# LED_Board_control.net
KiCad netlist of a schematic drawn in Altium Designer
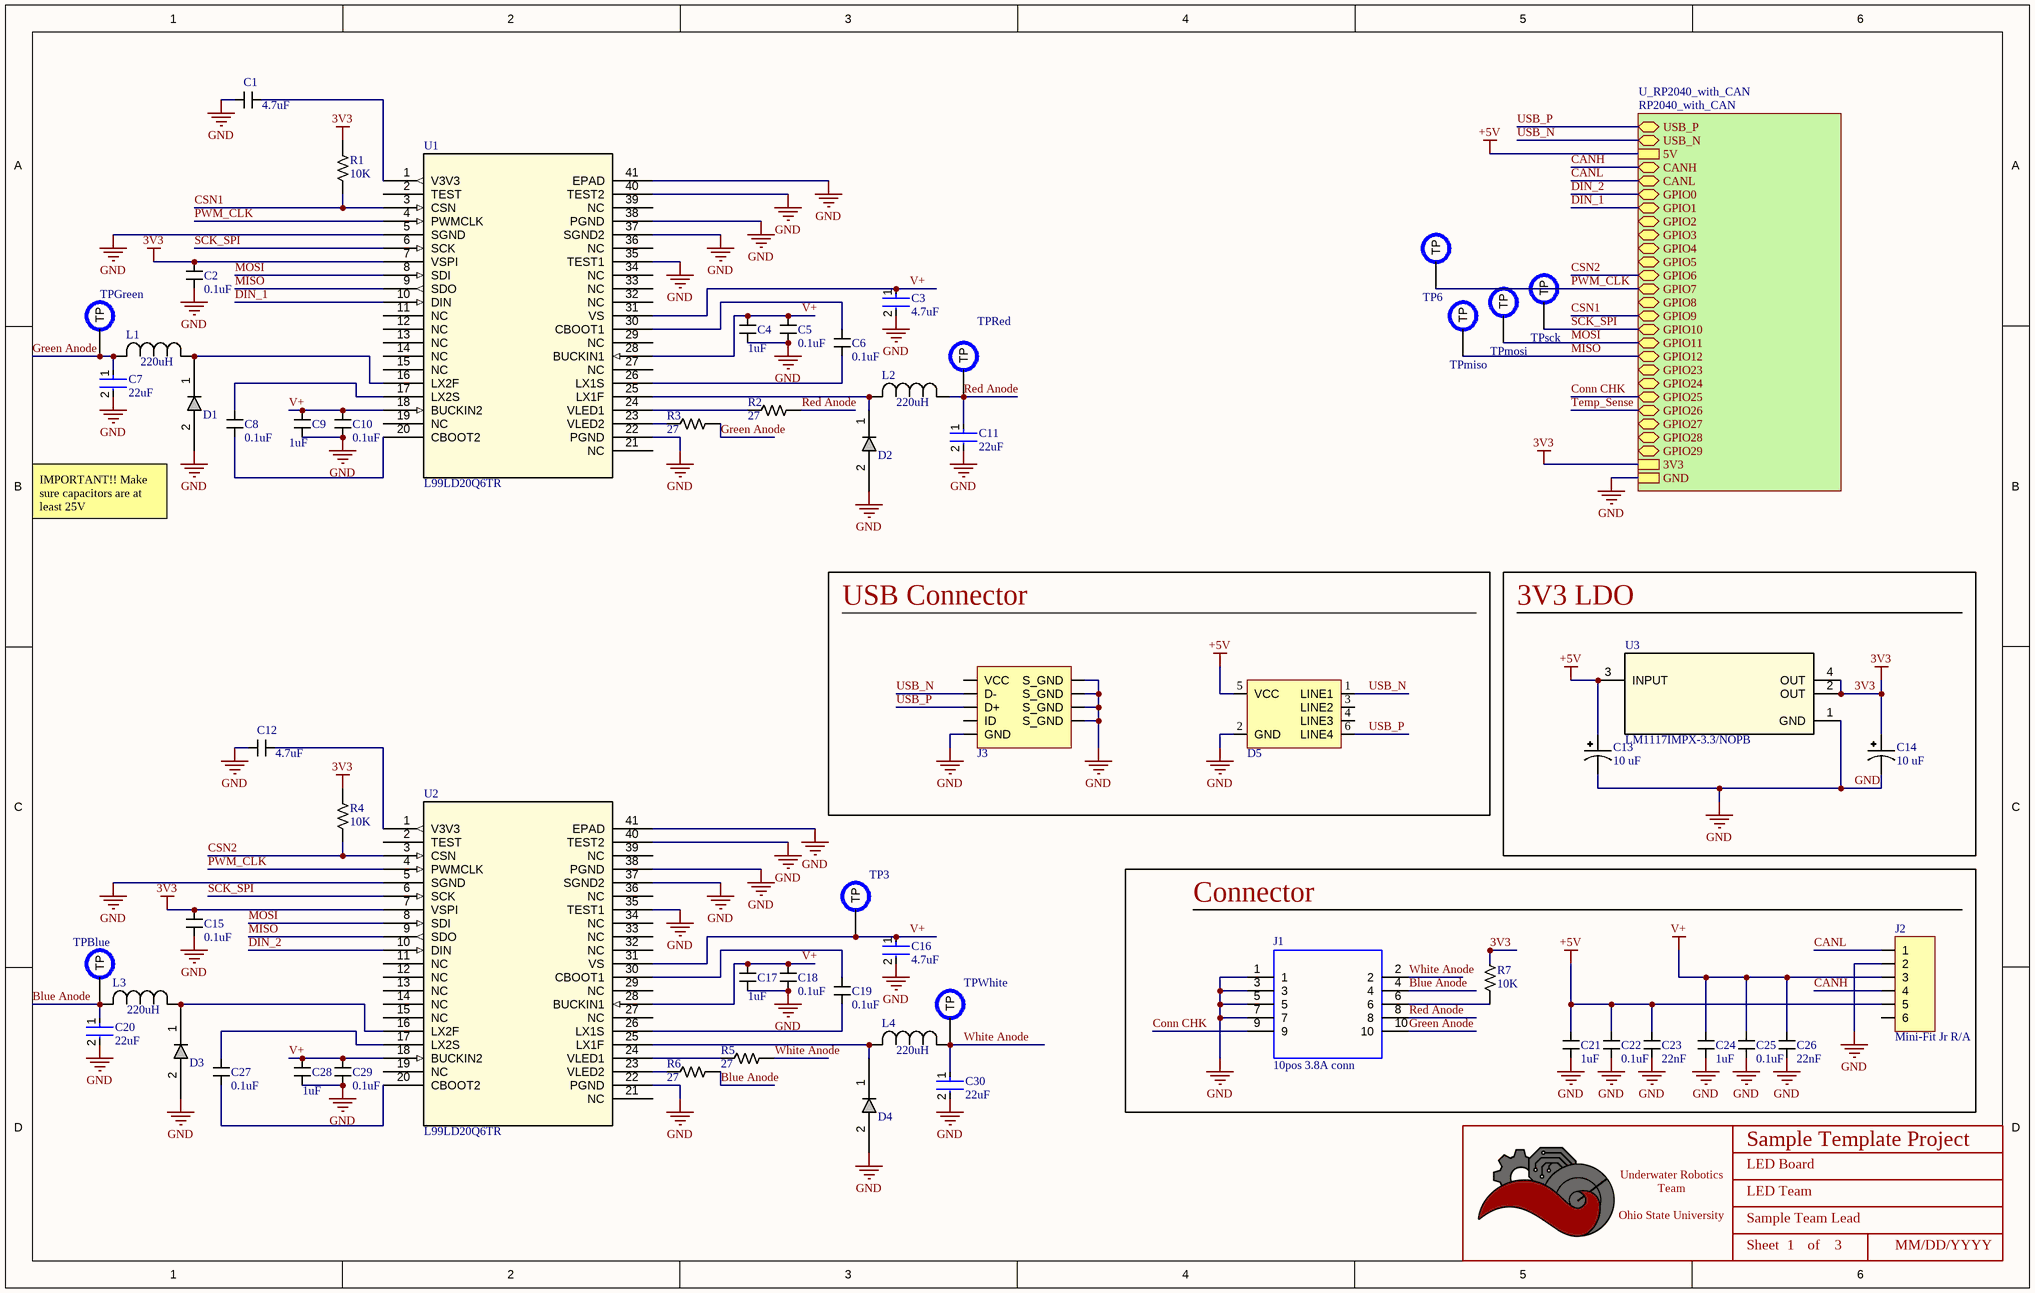
[diagram p0: LED_Board_control.SchDoc]

(export (version "E")
  (design (tool "Eeschema 10.0.6"))
  (components
    (comp (ref "*")
      (value "Title_Block")
      (footprint "LOGO")
      (description "UWRT Schematic Title Block Template\r\n\r\nCreated June 2021, Dylan Trainor")
      (libsource (lib "UWRT") (part "Title_Block"))
    )
    (comp (ref "C1")
      (value "4.7uF")
      (footprint "CAPACITOR_0603")
      (description "Cap 4.7uF 6.3V +/-10%\r\nCeramic 0603")
      (fields
        (field (name "TOLERANCE") "+/- 10%")
        (field (name "VOLTAGE") "6.3V")
        (field (name "MADE BY") "Robert Pafford")
      )
      (libsource (lib "Capacitors") (part "CAPACITOR_4.7uF_0603"))
    )
    (comp (ref "C2")
      (value "0.1uF")
      (footprint "CAPACITOR_0603")
      (description "Cap 100nF 6.3V +/-10%\r\nCeramic 0603")
      (fields
        (field (name "TOLERANCE") "+/- 10%")
        (field (name "VOLTAGE") "6.3V")
        (field (name "MADE BY") "Flip B")
      )
      (libsource (lib "Capacitors") (part "CAPACITOR_0.1uF_0603_1"))
    )
    (comp (ref "C3")
      (value "4.7uF")
      (footprint "CAPACITOR_0603")
      (description "Chip Multilayer Ceramic Capacitors for General Purpose, 0603, 4.7uF, X5R, 15%, 20%, 35V")
      (fields (field (name "TOLERANCE") "20%"))
      (libsource (lib "Capacitors") (part "CAP CERM 4.7UF 20% 35V"))
    )
    (comp (ref "C4")
      (value "1uF")
      (footprint "CAPACITOR_0603")
      (description "Cap 1uF 25V +/-10%\r\nCeramic 0603")
      (fields
        (field (name "TOLERANCE") "+/- 10%")
        (field (name "VOLTAGE") "16V")
        (field (name "MADE BY") "Flip B")
      )
      (libsource (lib "Capacitors") (part "CAPACITOR_1uF_0603_25V"))
    )
    (comp (ref "C5")
      (value "0.1uF")
      (footprint "CAPACITOR_0603")
      (description "Cap 100nF 25V +/-10%\r\nCeramic 0603")
      (fields
        (field (name "TOLERANCE") "+/- 10%")
        (field (name "VOLTAGE") "6.3V")
        (field (name "MADE BY") "Flip B")
      )
      (libsource (lib "Capacitors") (part "CAPACITOR_0.1uF_0603_25V"))
    )
    (comp (ref "C6")
      (value "0.1uF")
      (footprint "CAPACITOR_0603")
      (description "Cap 100nF 25V +/-10%\r\nCeramic 0603")
      (fields
        (field (name "TOLERANCE") "+/- 10%")
        (field (name "VOLTAGE") "6.3V")
        (field (name "MADE BY") "Flip B")
      )
      (libsource (lib "Capacitors") (part "CAPACITOR_0.1uF_0603_25V"))
    )
    (comp (ref "C7")
      (value "22uF")
      (footprint "FP-C2012-125-0_2-MFG")
      (description "Multilayer Ceramic Capacitors 22μF ±20% 35V X5R SMD 0805")
      (fields (field (name "TOLERANCE") "20%"))
      (libsource (lib "Altium Content Vault") (part "b4654b650e69147ec39a6b967a45e02"))
    )
    (comp (ref "C8")
      (value "0.1uF")
      (footprint "CAPACITOR_0603")
      (description "Cap 100nF 25V +/-10%\r\nCeramic 0603")
      (fields
        (field (name "TOLERANCE") "+/- 10%")
        (field (name "VOLTAGE") "6.3V")
        (field (name "MADE BY") "Flip B")
      )
      (libsource (lib "Capacitors") (part "CAPACITOR_0.1uF_0603_25V"))
    )
    (comp (ref "C9")
      (value "1uF")
      (footprint "CAPACITOR_0603")
      (description "Cap 1uF 25V +/-10%\r\nCeramic 0603")
      (fields
        (field (name "TOLERANCE") "+/- 10%")
        (field (name "VOLTAGE") "16V")
        (field (name "MADE BY") "Flip B")
      )
      (libsource (lib "Capacitors") (part "CAPACITOR_1uF_0603_25V"))
    )
    (comp (ref "C10")
      (value "0.1uF")
      (footprint "CAPACITOR_0603")
      (description "Cap 100nF 25V +/-10%\r\nCeramic 0603")
      (fields
        (field (name "TOLERANCE") "+/- 10%")
        (field (name "VOLTAGE") "6.3V")
        (field (name "MADE BY") "Flip B")
      )
      (libsource (lib "Capacitors") (part "CAPACITOR_0.1uF_0603_25V"))
    )
    (comp (ref "C11")
      (value "22uF")
      (footprint "FP-C2012-125-0_2-MFG")
      (description "Multilayer Ceramic Capacitors 22μF ±20% 35V X5R SMD 0805")
      (fields (field (name "TOLERANCE") "20%"))
      (libsource (lib "Altium Content Vault") (part "b4654b650e69147ec39a6b967a45e02"))
    )
    (comp (ref "C12")
      (value "4.7uF")
      (footprint "CAPACITOR_0603")
      (description "Cap 4.7uF 6.3V +/-10%\r\nCeramic 0603")
      (fields
        (field (name "TOLERANCE") "+/- 10%")
        (field (name "VOLTAGE") "6.3V")
        (field (name "MADE BY") "Robert Pafford")
      )
      (libsource (lib "Capacitors") (part "CAPACITOR_4.7uF_0603"))
    )
    (comp (ref "C13")
      (value "10uF Tantalum 16V")
      (footprint "CAPACITOR_1206 - POLAR")
      (description "Cap 10uF 16V +/-20%\r\nTantalum 1206")
      (fields
        (field (name "TOLERANCE") "+/- 10%")
        (field (name "VOLTAGE") "16V")
        (field (name "VALUE (UF)") "10 uF")
        (field (name "MADE BY") "Dylan T")
      )
      (libsource (lib "Capacitors") (part "CAPACITOR_10uF_1206_Tantalum_1"))
    )
    (comp (ref "C14")
      (value "10uF Tantalum 16V")
      (footprint "CAPACITOR_1206 - POLAR")
      (description "Cap 10uF 16V +/-20%\r\nTantalum 1206")
      (fields
        (field (name "TOLERANCE") "+/- 10%")
        (field (name "VOLTAGE") "16V")
        (field (name "VALUE (UF)") "10 uF")
        (field (name "MADE BY") "Dylan T")
      )
      (libsource (lib "Capacitors") (part "CAPACITOR_10uF_1206_Tantalum_1"))
    )
    (comp (ref "C15")
      (value "0.1uF")
      (footprint "CAPACITOR_0603")
      (description "Cap 100nF 6.3V +/-10%\r\nCeramic 0603")
      (fields
        (field (name "TOLERANCE") "+/- 10%")
        (field (name "VOLTAGE") "6.3V")
        (field (name "MADE BY") "Flip B")
      )
      (libsource (lib "Capacitors") (part "CAPACITOR_0.1uF_0603_1"))
    )
    (comp (ref "C16")
      (value "4.7uF")
      (footprint "CAPACITOR_0603")
      (description "Chip Multilayer Ceramic Capacitors for General Purpose, 0603, 4.7uF, X5R, 15%, 20%, 35V")
      (fields (field (name "TOLERANCE") "20%"))
      (libsource (lib "Capacitors") (part "CAP CERM 4.7UF 20% 35V"))
    )
    (comp (ref "C17")
      (value "1uF")
      (footprint "CAPACITOR_0603")
      (description "Cap 1uF 25V +/-10%\r\nCeramic 0603")
      (fields
        (field (name "TOLERANCE") "+/- 10%")
        (field (name "VOLTAGE") "16V")
        (field (name "MADE BY") "Flip B")
      )
      (libsource (lib "Capacitors") (part "CAPACITOR_1uF_0603_25V"))
    )
    (comp (ref "C18")
      (value "0.1uF")
      (footprint "CAPACITOR_0603")
      (description "Cap 100nF 25V +/-10%\r\nCeramic 0603")
      (fields
        (field (name "TOLERANCE") "+/- 10%")
        (field (name "VOLTAGE") "6.3V")
        (field (name "MADE BY") "Flip B")
      )
      (libsource (lib "Capacitors") (part "CAPACITOR_0.1uF_0603_25V"))
    )
    (comp (ref "C19")
      (value "0.1uF")
      (footprint "CAPACITOR_0603")
      (description "Cap 100nF 25V +/-10%\r\nCeramic 0603")
      (fields
        (field (name "TOLERANCE") "+/- 10%")
        (field (name "VOLTAGE") "6.3V")
        (field (name "MADE BY") "Flip B")
      )
      (libsource (lib "Capacitors") (part "CAPACITOR_0.1uF_0603_25V"))
    )
    (comp (ref "C20")
      (value "22uF")
      (footprint "FP-C2012-125-0_2-MFG")
      (description "Multilayer Ceramic Capacitors 22μF ±20% 35V X5R SMD 0805")
      (fields (field (name "TOLERANCE") "20%"))
      (libsource (lib "Altium Content Vault") (part "b4654b650e69147ec39a6b967a45e02"))
    )
    (comp (ref "C21")
      (value "1uF")
      (footprint "CAPACITOR_0603")
      (description "Cap 1uF 16V +/-10%\r\nCeramic 0603")
      (fields
        (field (name "TOLERANCE") "+/- 10%")
        (field (name "VOLTAGE") "16V")
        (field (name "MADE BY") "Flip B")
      )
      (libsource (lib "Capacitors") (part "CAPACITOR_1uF_0603"))
    )
    (comp (ref "C22")
      (value "0.1uF")
      (footprint "CAPACITOR_0805")
      (description "Cap 100nF 50V +/-10%\r\nCeramic 0805")
      (fields
        (field (name "TOLERANCE") "+/- 10%")
        (field (name "VOLTAGE") "50V")
        (field (name "MADE BY") "Robert Pafford")
      )
      (libsource (lib "Capacitors") (part "CAPACITOR_0.1uF_0805"))
    )
    (comp (ref "C23")
      (value "22nF")
      (footprint "CAPACITOR_0402")
      (description "Cap 22nF 25V +/-10%\r\nCeramic 0402")
      (fields
        (field (name "TOLERANCE") "+/- 10%")
        (field (name "VOLTAGE") "25V")
        (field (name "MADE BY") "Robert Pafford")
      )
      (libsource (lib "Capacitors") (part "CAPACITOR_0.022uF_0402"))
    )
    (comp (ref "C24")
      (value "1uF")
      (footprint "CAPACITOR_0603")
      (description "Cap 1uF 16V +/-10%\r\nCeramic 0603")
      (fields
        (field (name "TOLERANCE") "+/- 10%")
        (field (name "VOLTAGE") "16V")
        (field (name "MADE BY") "Flip B")
      )
      (libsource (lib "Capacitors") (part "CAPACITOR_1uF_0603"))
    )
    (comp (ref "C25")
      (value "0.1uF")
      (footprint "CAPACITOR_0805")
      (description "Cap 100nF 50V +/-10%\r\nCeramic 0805")
      (fields
        (field (name "TOLERANCE") "+/- 10%")
        (field (name "VOLTAGE") "50V")
        (field (name "MADE BY") "Robert Pafford")
      )
      (libsource (lib "Capacitors") (part "CAPACITOR_0.1uF_0805"))
    )
    (comp (ref "C26")
      (value "22nF")
      (footprint "CAPACITOR_0402")
      (description "Cap 22nF 25V +/-10%\r\nCeramic 0402")
      (fields
        (field (name "TOLERANCE") "+/- 10%")
        (field (name "VOLTAGE") "25V")
        (field (name "MADE BY") "Robert Pafford")
      )
      (libsource (lib "Capacitors") (part "CAPACITOR_0.022uF_0402"))
    )
    (comp (ref "C27")
      (value "0.1uF")
      (footprint "CAPACITOR_0603")
      (description "Cap 100nF 25V +/-10%\r\nCeramic 0603")
      (fields
        (field (name "TOLERANCE") "+/- 10%")
        (field (name "VOLTAGE") "6.3V")
        (field (name "MADE BY") "Flip B")
      )
      (libsource (lib "Capacitors") (part "CAPACITOR_0.1uF_0603_25V"))
    )
    (comp (ref "C28")
      (value "1uF")
      (footprint "CAPACITOR_0603")
      (description "Cap 1uF 25V +/-10%\r\nCeramic 0603")
      (fields
        (field (name "TOLERANCE") "+/- 10%")
        (field (name "VOLTAGE") "16V")
        (field (name "MADE BY") "Flip B")
      )
      (libsource (lib "Capacitors") (part "CAPACITOR_1uF_0603_25V"))
    )
    (comp (ref "C29")
      (value "0.1uF")
      (footprint "CAPACITOR_0603")
      (description "Cap 100nF 25V +/-10%\r\nCeramic 0603")
      (fields
        (field (name "TOLERANCE") "+/- 10%")
        (field (name "VOLTAGE") "6.3V")
        (field (name "MADE BY") "Flip B")
      )
      (libsource (lib "Capacitors") (part "CAPACITOR_0.1uF_0603_25V"))
    )
    (comp (ref "C30")
      (value "22uF")
      (footprint "FP-C2012-125-0_2-MFG")
      (description "Multilayer Ceramic Capacitors 22μF ±20% 35V X5R SMD 0805")
      (fields (field (name "TOLERANCE") "20%"))
      (libsource (lib "Altium Content Vault") (part "b4654b650e69147ec39a6b967a45e02"))
    )
    (comp (ref "D1")
      (value "CCS15S40,L3F")
      (footprint "SOD-963   CST2C_TOS")
      (description "DIODE SCHOTTKY 40V 1.5A CST2C")
      (fields (field (name "COPYRIGHT") "Copyright (C) 2023 Ultra Librarian. All rights reserved."))
      (libsource (lib "Diodes") (part "SCHOTTKY_40V_1.5A"))
    )
    (comp (ref "D2")
      (value "CCS15S40,L3F")
      (footprint "SOD-963   CST2C_TOS")
      (description "DIODE SCHOTTKY 40V 1.5A CST2C")
      (fields (field (name "COPYRIGHT") "Copyright (C) 2023 Ultra Librarian. All rights reserved."))
      (libsource (lib "Diodes") (part "SCHOTTKY_40V_1.5A"))
    )
    (comp (ref "D3")
      (value "CCS15S40,L3F")
      (footprint "SOD-963   CST2C_TOS")
      (description "DIODE SCHOTTKY 40V 1.5A CST2C")
      (fields (field (name "COPYRIGHT") "Copyright (C) 2023 Ultra Librarian. All rights reserved."))
      (libsource (lib "Diodes") (part "SCHOTTKY_40V_1.5A"))
    )
    (comp (ref "D4")
      (value "CCS15S40,L3F")
      (footprint "SOD-963   CST2C_TOS")
      (description "DIODE SCHOTTKY 40V 1.5A CST2C")
      (fields (field (name "COPYRIGHT") "Copyright (C) 2023 Ultra Librarian. All rights reserved."))
      (libsource (lib "Diodes") (part "SCHOTTKY_40V_1.5A"))
    )
    (comp (ref "D5")
      (value "TVS DIODE 5VWM 25VC SOT23-6")
      (footprint "SOT 23-6L")
      (description "25V Clamp 6A (8/20µs) Ipp Tvs Diode Surface Mount SOT-23-6")
      (fields (field (name "MADE BY") "Robert Pafford"))
      (libsource (lib "Diodes") (part "RCLAMP0504S.TCT"))
    )
    (comp (ref "J1")
      (value "10pos 3.8A conn")
      (footprint "Connectors:SAMTEC-LS2-105-01-X-D-RA1")
      (description "10 Position Connector Self Mating, Non-Gendered, Hermaphroditic Through Hole, Right Angle Gold")
      (fields (field (name "MP") "SAMTEC-LS2-105-01-X-D-RA1"))
      (libsource (lib "Connectors") (part "SAMTEC-LS2-105-01-X-D-RA1"))
    )
    (comp (ref "J2")
      (value "Mini-Fit Jr R/A")
      (footprint "CONN_MOLEX_MINIFIT JR_6 POS_R/A")
      (description "Molex Minifit Jr. 5569 \r\n6 Pos R/A Natural")
      (fields (field (name "MANUFACTURER") "Molex") (field (name "CREATED BY") "Flip B"))
      (libsource (lib "Connectors") (part "CONN_MOLEX_MINIFIT JR_6POS_R/A"))
    )
    (comp (ref "J3")
      (value "USB_MICRO R/A")
      (footprint "CONN_MINIUSB")
      (description "Amphenol Micro USB-B\r\nUSB2.0 5 Pin Right Angle SMD")
      (fields (field (name "MANUFACTURER") "Amphenol") (field (name "CREATED BY") "Flip B"))
      (libsource (lib "Connectors") (part "CONN_MICROUSB"))
    )
    (comp (ref "L1")
      (value "SRR1280-221K")
      (footprint "IND_BOURNS_SRR1280")
      (description "220 µH Shielded Drum Core, Wirewound Inductor 1.6 A 400mOhm Max Nonstandard")
      (fields (field (name "COPYRIGHT") "Copyright (C) 2023 Ultra Librarian. All rights reserved."))
      (libsource (lib "Inductors") (part "INDUCTOR_SRR1280-221K"))
    )
    (comp (ref "L2")
      (value "SRR1280-221K")
      (footprint "IND_BOURNS_SRR1280")
      (description "220 µH Shielded Drum Core, Wirewound Inductor 1.6 A 400mOhm Max Nonstandard")
      (fields (field (name "COPYRIGHT") "Copyright (C) 2023 Ultra Librarian. All rights reserved."))
      (libsource (lib "Inductors") (part "INDUCTOR_SRR1280-221K"))
    )
    (comp (ref "L3")
      (value "SRR1280-221K")
      (footprint "IND_BOURNS_SRR1280")
      (description "220 µH Shielded Drum Core, Wirewound Inductor 1.6 A 400mOhm Max Nonstandard")
      (fields (field (name "COPYRIGHT") "Copyright (C) 2023 Ultra Librarian. All rights reserved."))
      (libsource (lib "Inductors") (part "INDUCTOR_SRR1280-221K"))
    )
    (comp (ref "L4")
      (value "SRR1280-221K")
      (footprint "IND_BOURNS_SRR1280")
      (description "220 µH Shielded Drum Core, Wirewound Inductor 1.6 A 400mOhm Max Nonstandard")
      (fields (field (name "COPYRIGHT") "Copyright (C) 2023 Ultra Librarian. All rights reserved."))
      (libsource (lib "Inductors") (part "INDUCTOR_SRR1280-221K"))
    )
    (comp (ref "R1")
      (value "10k Ohm 1% 1/16W")
      (footprint "RESISTOR_0402")
      (description "RES 10k OHM 1% 1/16W 0402")
      (fields
        (field (name "TOLERANCE") "+/- 1%")
        (field (name "VALUE  (OHMS)") "10K")
        (field (name "MADE BY") "Robert Pafford")
      )
      (libsource (lib "Resistors") (part "RESISTOR_10K_0402"))
    )
    (comp (ref "R2")
      (value "27 Ohm 5% 1/8W")
      (footprint "RESISTOR_0603")
      (description "RES 27 OHM 5% 1/8W 0603")
      (fields
        (field (name "TOLERANCE") "+/- 5%")
        (field (name "VALUE  (OHMS)") "27")
        (field (name "MADE BY") "Robert Pafford")
      )
      (libsource (lib "Resistors") (part "RESISTOR_27_0603"))
    )
    (comp (ref "R3")
      (value "27 Ohm 5% 1/8W")
      (footprint "RESISTOR_0603")
      (description "RES 27 OHM 5% 1/8W 0603")
      (fields
        (field (name "TOLERANCE") "+/- 5%")
        (field (name "VALUE  (OHMS)") "27")
        (field (name "MADE BY") "Robert Pafford")
      )
      (libsource (lib "Resistors") (part "RESISTOR_27_0603"))
    )
    (comp (ref "R4")
      (value "10k Ohm 1% 1/16W")
      (footprint "RESISTOR_0402")
      (description "RES 10k OHM 1% 1/16W 0402")
      (fields
        (field (name "TOLERANCE") "+/- 1%")
        (field (name "VALUE  (OHMS)") "10K")
        (field (name "MADE BY") "Robert Pafford")
      )
      (libsource (lib "Resistors") (part "RESISTOR_10K_0402"))
    )
    (comp (ref "R5")
      (value "27 Ohm 5% 1/8W")
      (footprint "RESISTOR_0603")
      (description "RES 27 OHM 5% 1/8W 0603")
      (fields
        (field (name "TOLERANCE") "+/- 5%")
        (field (name "VALUE  (OHMS)") "27")
        (field (name "MADE BY") "Robert Pafford")
      )
      (libsource (lib "Resistors") (part "RESISTOR_27_0603"))
    )
    (comp (ref "R6")
      (value "27 Ohm 5% 1/8W")
      (footprint "RESISTOR_0603")
      (description "RES 27 OHM 5% 1/8W 0603")
      (fields
        (field (name "TOLERANCE") "+/- 5%")
        (field (name "VALUE  (OHMS)") "27")
        (field (name "MADE BY") "Robert Pafford")
      )
      (libsource (lib "Resistors") (part "RESISTOR_27_0603"))
    )
    (comp (ref "R7")
      (value "10k Ohm 0.5% 1/10W")
      (footprint "RESISTOR_0603")
      (description "RES 10k OHM 0.5% 1/10W 0603")
      (fields
        (field (name "TOLERANCE") "+/- 0.5%")
        (field (name "VALUE  (OHMS)") "10K")
        (field (name "MADE BY") "Robert Pafford")
      )
      (libsource (lib "Resistors") (part "RESISTOR_10K_0.5%_0603"))
    )
    (comp (ref "TP3")
      (value "PCB Test Point")
      (footprint "TESTPOINT_1.2MM")
      (fields (field (name "MADE BY") "Robert Pafford"))
      (libsource (lib "Connectors") (part "TESTPOINT"))
    )
    (comp (ref "TP6")
      (value "PCB Test Point")
      (footprint "TESTPOINT_1.2MM")
      (fields (field (name "MADE BY") "Robert Pafford"))
      (libsource (lib "Connectors") (part "TESTPOINT"))
    )
    (comp (ref "TPBlue")
      (value "PCB Test Point")
      (footprint "TESTPOINT_1.2MM")
      (fields (field (name "MADE BY") "Robert Pafford"))
      (libsource (lib "Connectors") (part "TESTPOINT"))
    )
    (comp (ref "TPGreen")
      (value "PCB Test Point")
      (footprint "TESTPOINT_1.2MM")
      (fields (field (name "MADE BY") "Robert Pafford"))
      (libsource (lib "Connectors") (part "TESTPOINT"))
    )
    (comp (ref "TPmiso")
      (value "PCB Test Point")
      (footprint "TESTPOINT_1.2MM")
      (fields (field (name "MADE BY") "Robert Pafford"))
      (libsource (lib "Connectors") (part "TESTPOINT"))
    )
    (comp (ref "TPmosi")
      (value "PCB Test Point")
      (footprint "TESTPOINT_1.2MM")
      (fields (field (name "MADE BY") "Robert Pafford"))
      (libsource (lib "Connectors") (part "TESTPOINT"))
    )
    (comp (ref "TPRed")
      (value "PCB Test Point")
      (footprint "TESTPOINT_1.2MM")
      (fields (field (name "MADE BY") "Robert Pafford"))
      (libsource (lib "Connectors") (part "TESTPOINT"))
    )
    (comp (ref "TPsck")
      (value "PCB Test Point")
      (footprint "TESTPOINT_1.2MM")
      (fields (field (name "MADE BY") "Robert Pafford"))
      (libsource (lib "Connectors") (part "TESTPOINT"))
    )
    (comp (ref "TPWhite")
      (value "PCB Test Point")
      (footprint "TESTPOINT_1.2MM")
      (fields (field (name "MADE BY") "Robert Pafford"))
      (libsource (lib "Connectors") (part "TESTPOINT"))
    )
    (comp (ref "U1")
      (value "L99LD20Q6TR")
      (footprint "L99LD20Q6TR")
      (description "IC LED DRVR RGLTR PWM 1.5A 40QFN")
      (fields (field (name "COPYRIGHT") "Copyright (C) 2023 Ultra Librarian. All rights reserved."))
      (libsource (lib "Integrated Circuits") (part "L99LD20Q6TR"))
    )
    (comp (ref "U2")
      (value "L99LD20Q6TR")
      (footprint "L99LD20Q6TR")
      (description "IC LED DRVR RGLTR PWM 1.5A 40QFN")
      (fields (field (name "COPYRIGHT") "Copyright (C) 2023 Ultra Librarian. All rights reserved."))
      (libsource (lib "Integrated Circuits") (part "L99LD20Q6TR"))
    )
    (comp (ref "U3")
      (value "LM1117IMPX-3.3/NOPB")
      (footprint "SOT-223-4")
      (description "IC REG LIN 3.3V 800MA SOT223-4")
      (fields
        (field (name "PARTNUMBER") "LM1117IMP-3.3/NOPB")
        (field (name "MANUFACTURER") "Texas Instruments")
        (field (name "CREATED BY") "Dylan T")
      )
      (libsource (lib "Converter") (part "LM1117IMPX-3.3/NOPB"))
    )
  )
  (nets
    (net (code "1") (name "+5V") (class "Default")
      (node (ref "C13") (pin "1") (pintype "passive"))
      (node (ref "C21") (pin "1") (pinfunction "1_1") (pintype "passive"))
      (node (ref "C22") (pin "1") (pinfunction "1_1") (pintype "passive"))
      (node (ref "C23") (pin "1") (pinfunction "1_1") (pintype "passive"))
      (node (ref "D5") (pin "5") (pinfunction "VCC_5") (pintype "power_in"))
      (node (ref "J2") (pin "5") (pinfunction "5_5") (pintype "passive"))
      (node (ref "U3") (pin "3") (pinfunction "INPUT_3") (pintype "power_in"))
    )
    (net (code "2") (name "/Blue Anode") (class "Default")
      (node (ref "C20") (pin "1") (pinfunction "1_1") (pintype "passive"))
      (node (ref "J1") (pin "4") (pinfunction "4_4") (pintype "passive"))
      (node (ref "L3") (pin "2") (pinfunction "2_2") (pintype "passive"))
      (node (ref "R6") (pin "1") (pinfunction "1_1") (pintype "passive"))
      (node (ref "TPBlue") (pin "TP") (pinfunction "TP_TP") (pintype "passive"))
    )
    (net (code "3") (name "/CANH") (class "Default")
      (node (ref "J2") (pin "4") (pinfunction "4_4") (pintype "passive"))
    )
    (net (code "4") (name "/CANL") (class "Default")
      (node (ref "J2") (pin "1") (pinfunction "1_1") (pintype "passive"))
    )
    (net (code "5") (name "/CSN1") (class "Default")
      (node (ref "R1") (pin "2") (pinfunction "2_2") (pintype "passive"))
      (node (ref "U1") (pin "3") (pinfunction "CSN_3") (pintype "input"))
    )
    (net (code "6") (name "/CSN2") (class "Default")
      (node (ref "R4") (pin "2") (pinfunction "2_2") (pintype "passive"))
      (node (ref "U2") (pin "3") (pinfunction "CSN_3") (pintype "input"))
    )
    (net (code "7") (name "/Conn CHK") (class "Default")
      (node (ref "J1") (pin "9") (pinfunction "9_9") (pintype "passive"))
    )
    (net (code "8") (name "/DIN_1") (class "Default")
      (node (ref "U1") (pin "10") (pinfunction "DIN_10") (pintype "input"))
    )
    (net (code "9") (name "/DIN_2") (class "Default")
      (node (ref "U2") (pin "10") (pinfunction "DIN_10") (pintype "input"))
    )
    (net (code "20") (name "/Green Anode") (class "Default")
      (node (ref "C7") (pin "1") (pinfunction "1_1") (pintype "passive"))
      (node (ref "J1") (pin "10") (pinfunction "10_10") (pintype "passive"))
      (node (ref "L1") (pin "2") (pinfunction "2_2") (pintype "passive"))
      (node (ref "R3") (pin "1") (pinfunction "1_1") (pintype "passive"))
      (node (ref "TPGreen") (pin "TP") (pinfunction "TP_TP") (pintype "passive"))
    )
    (net (code "21") (name "/MISO") (class "Default")
      (node (ref "TPmiso") (pin "TP") (pinfunction "TP_TP") (pintype "passive"))
      (node (ref "U1") (pin "9") (pinfunction "SDO_9") (pintype "output"))
      (node (ref "U2") (pin "9") (pinfunction "SDO_9") (pintype "output"))
    )
    (net (code "22") (name "/MOSI") (class "Default")
      (node (ref "TPmosi") (pin "TP") (pinfunction "TP_TP") (pintype "passive"))
      (node (ref "U1") (pin "8") (pinfunction "SDI_8") (pintype "input"))
      (node (ref "U2") (pin "8") (pinfunction "SDI_8") (pintype "input"))
    )
    (net (code "23") (name "/PWM_CLK") (class "Default")
      (node (ref "TP6") (pin "TP") (pinfunction "TP_TP") (pintype "passive"))
      (node (ref "U1") (pin "4") (pinfunction "PWMCLK_4") (pintype "input"))
      (node (ref "U2") (pin "4") (pinfunction "PWMCLK_4") (pintype "input"))
    )
    (net (code "24") (name "/Red Anode") (class "Default")
      (node (ref "C11") (pin "1") (pinfunction "1_1") (pintype "passive"))
      (node (ref "J1") (pin "8") (pinfunction "8_8") (pintype "passive"))
      (node (ref "L2") (pin "1") (pinfunction "1_1") (pintype "passive"))
      (node (ref "R2") (pin "1") (pinfunction "1_1") (pintype "passive"))
      (node (ref "TPRed") (pin "TP") (pinfunction "TP_TP") (pintype "passive"))
    )
    (net (code "25") (name "/SCK_SPI") (class "Default")
      (node (ref "TPsck") (pin "TP") (pinfunction "TP_TP") (pintype "passive"))
      (node (ref "U1") (pin "6") (pinfunction "SCK_6") (pintype "input"))
      (node (ref "U2") (pin "6") (pinfunction "SCK_6") (pintype "input"))
    )
    (net (code "27") (name "/USB_N") (class "Default")
      (node (ref "D5") (pin "1") (pinfunction "LINE1_1") (pintype "passive"))
      (node (ref "J3") (pin "2") (pinfunction "D-_2") (pintype "passive"))
    )
    (net (code "28") (name "/USB_P") (class "Default")
      (node (ref "D5") (pin "6") (pinfunction "LINE4_6") (pintype "passive"))
      (node (ref "J3") (pin "3") (pinfunction "D+_3") (pintype "passive"))
    )
    (net (code "29") (name "/White Anode") (class "Default")
      (node (ref "C30") (pin "1") (pinfunction "1_1") (pintype "passive"))
      (node (ref "J1") (pin "2") (pinfunction "2_2") (pintype "passive"))
      (node (ref "L4") (pin "1") (pinfunction "1_1") (pintype "passive"))
      (node (ref "R5") (pin "1") (pinfunction "1_1") (pintype "passive"))
      (node (ref "TPWhite") (pin "TP") (pinfunction "TP_TP") (pintype "passive"))
    )
    (net (code "30") (name "3V3") (class "Default")
      (node (ref "C14") (pin "1") (pintype "passive"))
      (node (ref "C15") (pin "1") (pinfunction "1_1") (pintype "passive"))
      (node (ref "C2") (pin "1") (pinfunction "1_1") (pintype "passive"))
      (node (ref "R1") (pin "1") (pinfunction "1_1") (pintype "passive"))
      (node (ref "R4") (pin "1") (pinfunction "1_1") (pintype "passive"))
      (node (ref "R7") (pin "1") (pinfunction "1_1") (pintype "passive"))
      (node (ref "U1") (pin "7") (pinfunction "VSPI_7") (pintype "passive"))
      (node (ref "U2") (pin "7") (pinfunction "VSPI_7") (pintype "passive"))
      (node (ref "U3") (pin "2") (pinfunction "OUT_2") (pintype "power_in"))
      (node (ref "U3") (pin "4") (pinfunction "OUT_4") (pintype "power_in"))
    )
    (net (code "31") (name "GND") (class "Default")
      (node (ref "C1") (pin "2") (pinfunction "2_2") (pintype "passive"))
      (node (ref "C10") (pin "2") (pinfunction "2_2") (pintype "passive"))
      (node (ref "C11") (pin "2") (pinfunction "2_2") (pintype "passive"))
      (node (ref "C12") (pin "2") (pinfunction "2_2") (pintype "passive"))
      (node (ref "C13") (pin "2") (pintype "passive"))
      (node (ref "C14") (pin "2") (pintype "passive"))
      (node (ref "C15") (pin "2") (pinfunction "2_2") (pintype "passive"))
      (node (ref "C16") (pin "2") (pinfunction "2_2") (pintype "passive"))
      (node (ref "C17") (pin "1") (pinfunction "1_1") (pintype "passive"))
      (node (ref "C18") (pin "2") (pinfunction "2_2") (pintype "passive"))
      (node (ref "C2") (pin "2") (pinfunction "2_2") (pintype "passive"))
      (node (ref "C20") (pin "2") (pinfunction "2_2") (pintype "passive"))
      (node (ref "C21") (pin "2") (pinfunction "2_2") (pintype "passive"))
      (node (ref "C22") (pin "2") (pinfunction "2_2") (pintype "passive"))
      (node (ref "C23") (pin "2") (pinfunction "2_2") (pintype "passive"))
      (node (ref "C24") (pin "2") (pinfunction "2_2") (pintype "passive"))
      (node (ref "C25") (pin "2") (pinfunction "2_2") (pintype "passive"))
      (node (ref "C26") (pin "2") (pinfunction "2_2") (pintype "passive"))
      (node (ref "C28") (pin "1") (pinfunction "1_1") (pintype "passive"))
      (node (ref "C29") (pin "2") (pinfunction "2_2") (pintype "passive"))
      (node (ref "C3") (pin "2") (pinfunction "2_2") (pintype "passive"))
      (node (ref "C30") (pin "2") (pinfunction "2_2") (pintype "passive"))
      (node (ref "C4") (pin "1") (pinfunction "1_1") (pintype "passive"))
      (node (ref "C5") (pin "2") (pinfunction "2_2") (pintype "passive"))
      (node (ref "C7") (pin "2") (pinfunction "2_2") (pintype "passive"))
      (node (ref "C9") (pin "1") (pinfunction "1_1") (pintype "passive"))
      (node (ref "D1") (pin "2") (pinfunction "2_2") (pintype "passive"))
      (node (ref "D2") (pin "2") (pinfunction "2_2") (pintype "passive"))
      (node (ref "D3") (pin "2") (pinfunction "2_2") (pintype "passive"))
      (node (ref "D4") (pin "2") (pinfunction "2_2") (pintype "passive"))
      (node (ref "D5") (pin "2") (pinfunction "GND_2") (pintype "power_in"))
      (node (ref "J1") (pin "1") (pinfunction "1_1") (pintype "passive"))
      (node (ref "J1") (pin "3") (pinfunction "3_3") (pintype "passive"))
      (node (ref "J1") (pin "5") (pinfunction "5_5") (pintype "passive"))
      (node (ref "J1") (pin "7") (pinfunction "7_7") (pintype "passive"))
      (node (ref "J2") (pin "2") (pinfunction "2_2") (pintype "passive"))
      (node (ref "J3") (pin "5") (pinfunction "GND_5") (pintype "passive"))
      (node (ref "J3") (pin "6") (pinfunction "S_GND_6") (pintype "passive"))
      (node (ref "J3") (pin "7") (pinfunction "S_GND_7") (pintype "passive"))
      (node (ref "J3") (pin "8") (pinfunction "S_GND_8") (pintype "passive"))
      (node (ref "J3") (pin "9") (pinfunction "S_GND_9") (pintype "passive"))
      (node (ref "U1") (pin "22") (pinfunction "PGND_22") (pintype "power_in"))
      (node (ref "U1") (pin "35") (pinfunction "TEST1_35") (pintype "passive"))
      (node (ref "U1") (pin "37") (pinfunction "SGND2_37") (pintype "power_in"))
      (node (ref "U1") (pin "38") (pinfunction "PGND_38") (pintype "power_in"))
      (node (ref "U1") (pin "40") (pinfunction "TEST2_40") (pintype "passive"))
      (node (ref "U1") (pin "41") (pinfunction "EPAD_41") (pintype "power_in"))
      (node (ref "U1") (pin "5") (pinfunction "SGND_5") (pintype "power_in"))
      (node (ref "U2") (pin "22") (pinfunction "PGND_22") (pintype "power_in"))
      (node (ref "U2") (pin "35") (pinfunction "TEST1_35") (pintype "passive"))
      (node (ref "U2") (pin "37") (pinfunction "SGND2_37") (pintype "power_in"))
      (node (ref "U2") (pin "38") (pinfunction "PGND_38") (pintype "power_in"))
      (node (ref "U2") (pin "40") (pinfunction "TEST2_40") (pintype "passive"))
      (node (ref "U2") (pin "41") (pinfunction "EPAD_41") (pintype "power_in"))
      (node (ref "U2") (pin "5") (pinfunction "SGND_5") (pintype "power_in"))
      (node (ref "U3") (pin "1") (pinfunction "GND_1") (pintype "power_in"))
    )
    (net (code "32") (name "Net-(J1-Pad6)") (class "Default")
      (node (ref "J1") (pin "6") (pinfunction "6_6") (pintype "passive"))
      (node (ref "R7") (pin "2") (pinfunction "2_2") (pintype "passive"))
    )
    (net (code "33") (name "Net-(U1-CBOOT1)") (class "Default")
      (node (ref "C6") (pin "1") (pinfunction "1_1") (pintype "passive"))
      (node (ref "U1") (pin "30") (pinfunction "CBOOT1_30") (pintype "passive"))
    )
    (net (code "34") (name "Net-(U1-CBOOT2)") (class "Default")
      (node (ref "C8") (pin "2") (pinfunction "2_2") (pintype "passive"))
      (node (ref "U1") (pin "20") (pinfunction "CBOOT2_20") (pintype "passive"))
    )
    (net (code "35") (name "Net-(U1-LX1F)") (class "Default")
      (node (ref "D2") (pin "1") (pinfunction "1_1") (pintype "passive"))
      (node (ref "L2") (pin "2") (pinfunction "2_2") (pintype "passive"))
      (node (ref "U1") (pin "25") (pinfunction "LX1F_25") (pintype "passive"))
    )
    (net (code "36") (name "Net-(U1-LX1S)") (class "Default")
      (node (ref "C6") (pin "2") (pinfunction "2_2") (pintype "passive"))
      (node (ref "U1") (pin "26") (pinfunction "LX1S_26") (pintype "passive"))
    )
    (net (code "37") (name "Net-(U1-LX2F)") (class "Default")
      (node (ref "D1") (pin "1") (pinfunction "1_1") (pintype "passive"))
      (node (ref "L1") (pin "1") (pinfunction "1_1") (pintype "passive"))
      (node (ref "U1") (pin "16") (pinfunction "LX2F_16") (pintype "passive"))
    )
    (net (code "38") (name "Net-(U1-LX2S)") (class "Default")
      (node (ref "C8") (pin "1") (pinfunction "1_1") (pintype "passive"))
      (node (ref "U1") (pin "17") (pinfunction "LX2S_17") (pintype "passive"))
    )
    (net (code "39") (name "Net-(U1-V3V3)") (class "Default")
      (node (ref "C1") (pin "1") (pinfunction "1_1") (pintype "passive"))
      (node (ref "U1") (pin "1") (pinfunction "V3V3_1") (pintype "output"))
    )
    (net (code "40") (name "Net-(U1-VLED1)") (class "Default")
      (node (ref "R2") (pin "2") (pinfunction "2_2") (pintype "passive"))
      (node (ref "U1") (pin "24") (pinfunction "VLED1_24") (pintype "passive"))
    )
    (net (code "41") (name "Net-(U1-VLED2)") (class "Default")
      (node (ref "R3") (pin "2") (pinfunction "2_2") (pintype "passive"))
      (node (ref "U1") (pin "23") (pinfunction "VLED2_23") (pintype "passive"))
    )
    (net (code "42") (name "Net-(U2-CBOOT1)") (class "Default")
      (node (ref "C19") (pin "1") (pinfunction "1_1") (pintype "passive"))
      (node (ref "U2") (pin "30") (pinfunction "CBOOT1_30") (pintype "passive"))
    )
    (net (code "43") (name "Net-(U2-CBOOT2)") (class "Default")
      (node (ref "C27") (pin "2") (pinfunction "2_2") (pintype "passive"))
      (node (ref "U2") (pin "20") (pinfunction "CBOOT2_20") (pintype "passive"))
    )
    (net (code "44") (name "Net-(U2-LX1F)") (class "Default")
      (node (ref "D4") (pin "1") (pinfunction "1_1") (pintype "passive"))
      (node (ref "L4") (pin "2") (pinfunction "2_2") (pintype "passive"))
      (node (ref "U2") (pin "25") (pinfunction "LX1F_25") (pintype "passive"))
    )
    (net (code "45") (name "Net-(U2-LX1S)") (class "Default")
      (node (ref "C19") (pin "2") (pinfunction "2_2") (pintype "passive"))
      (node (ref "U2") (pin "26") (pinfunction "LX1S_26") (pintype "passive"))
    )
    (net (code "46") (name "Net-(U2-LX2F)") (class "Default")
      (node (ref "D3") (pin "1") (pinfunction "1_1") (pintype "passive"))
      (node (ref "L3") (pin "1") (pinfunction "1_1") (pintype "passive"))
      (node (ref "U2") (pin "16") (pinfunction "LX2F_16") (pintype "passive"))
    )
    (net (code "47") (name "Net-(U2-LX2S)") (class "Default")
      (node (ref "C27") (pin "1") (pinfunction "1_1") (pintype "passive"))
      (node (ref "U2") (pin "17") (pinfunction "LX2S_17") (pintype "passive"))
    )
    (net (code "48") (name "Net-(U2-V3V3)") (class "Default")
      (node (ref "C12") (pin "1") (pinfunction "1_1") (pintype "passive"))
      (node (ref "U2") (pin "1") (pinfunction "V3V3_1") (pintype "output"))
    )
    (net (code "49") (name "Net-(U2-VLED1)") (class "Default")
      (node (ref "R5") (pin "2") (pinfunction "2_2") (pintype "passive"))
      (node (ref "U2") (pin "24") (pinfunction "VLED1_24") (pintype "passive"))
    )
    (net (code "50") (name "Net-(U2-VLED2)") (class "Default")
      (node (ref "R6") (pin "2") (pinfunction "2_2") (pintype "passive"))
      (node (ref "U2") (pin "23") (pinfunction "VLED2_23") (pintype "passive"))
    )
    (net (code "51") (name "V+") (class "Default")
      (node (ref "C10") (pin "1") (pinfunction "1_1") (pintype "passive"))
      (node (ref "C16") (pin "1") (pinfunction "1_1") (pintype "passive"))
      (node (ref "C17") (pin "2") (pinfunction "2_2") (pintype "passive"))
      (node (ref "C18") (pin "1") (pinfunction "1_1") (pintype "passive"))
      (node (ref "C24") (pin "1") (pinfunction "1_1") (pintype "passive"))
      (node (ref "C25") (pin "1") (pinfunction "1_1") (pintype "passive"))
      (node (ref "C26") (pin "1") (pinfunction "1_1") (pintype "passive"))
      (node (ref "C28") (pin "2") (pinfunction "2_2") (pintype "passive"))
      (node (ref "C29") (pin "1") (pinfunction "1_1") (pintype "passive"))
      (node (ref "C3") (pin "1") (pinfunction "1_1") (pintype "passive"))
      (node (ref "C4") (pin "2") (pinfunction "2_2") (pintype "passive"))
      (node (ref "C5") (pin "1") (pinfunction "1_1") (pintype "passive"))
      (node (ref "C9") (pin "2") (pinfunction "2_2") (pintype "passive"))
      (node (ref "J2") (pin "3") (pinfunction "3_3") (pintype "passive"))
      (node (ref "TP3") (pin "TP") (pinfunction "TP_TP") (pintype "passive"))
      (node (ref "U1") (pin "18") (pinfunction "BUCKIN2_18") (pintype "input"))
      (node (ref "U1") (pin "28") (pinfunction "BUCKIN1_28") (pintype "input"))
      (node (ref "U1") (pin "31") (pinfunction "VS_31") (pintype "passive"))
      (node (ref "U2") (pin "18") (pinfunction "BUCKIN2_18") (pintype "input"))
      (node (ref "U2") (pin "28") (pinfunction "BUCKIN1_28") (pintype "input"))
      (node (ref "U2") (pin "31") (pinfunction "VS_31") (pintype "passive"))
    )
    (net (code "52") (name "unconnected-(D5-LINE2-Pad3)") (class "Default")
      (node (ref "D5") (pin "3") (pinfunction "LINE2_3") (pintype "passive"))
    )
    (net (code "53") (name "unconnected-(D5-LINE3-Pad4)") (class "Default")
      (node (ref "D5") (pin "4") (pinfunction "LINE3_4") (pintype "passive"))
    )
    (net (code "54") (name "unconnected-(J2-Pad6)") (class "Default")
      (node (ref "J2") (pin "6") (pinfunction "6_6") (pintype "passive"))
    )
    (net (code "55") (name "unconnected-(J3-ID-Pad4)") (class "Default")
      (node (ref "J3") (pin "4") (pinfunction "ID_4") (pintype "passive"))
    )
    (net (code "56") (name "unconnected-(J3-VCC-Pad1)") (class "Default")
      (node (ref "J3") (pin "1") (pinfunction "VCC_1") (pintype "passive"))
    )
    (net (code "57") (name "unconnected-(U1-NC-Pad11)") (class "Default")
      (node (ref "U1") (pin "11") (pinfunction "NC_11") (pintype "passive"))
    )
    (net (code "58") (name "unconnected-(U1-NC-Pad12)") (class "Default")
      (node (ref "U1") (pin "12") (pinfunction "NC_12") (pintype "passive"))
    )
    (net (code "59") (name "unconnected-(U1-NC-Pad13)") (class "Default")
      (node (ref "U1") (pin "13") (pinfunction "NC_13") (pintype "passive"))
    )
    (net (code "60") (name "unconnected-(U1-NC-Pad14)") (class "Default")
      (node (ref "U1") (pin "14") (pinfunction "NC_14") (pintype "passive"))
    )
    (net (code "61") (name "unconnected-(U1-NC-Pad15)") (class "Default")
      (node (ref "U1") (pin "15") (pinfunction "NC_15") (pintype "passive"))
    )
    (net (code "62") (name "unconnected-(U1-NC-Pad19)") (class "Default")
      (node (ref "U1") (pin "19") (pinfunction "NC_19") (pintype "passive"))
    )
    (net (code "63") (name "unconnected-(U1-NC-Pad21)") (class "Default")
      (node (ref "U1") (pin "21") (pinfunction "NC_21") (pintype "passive"))
    )
    (net (code "64") (name "unconnected-(U1-NC-Pad27)") (class "Default")
      (node (ref "U1") (pin "27") (pinfunction "NC_27") (pintype "passive"))
    )
    (net (code "65") (name "unconnected-(U1-NC-Pad29)") (class "Default")
      (node (ref "U1") (pin "29") (pinfunction "NC_29") (pintype "passive"))
    )
    (net (code "66") (name "unconnected-(U1-NC-Pad32)") (class "Default")
      (node (ref "U1") (pin "32") (pinfunction "NC_32") (pintype "passive"))
    )
    (net (code "67") (name "unconnected-(U1-NC-Pad33)") (class "Default")
      (node (ref "U1") (pin "33") (pinfunction "NC_33") (pintype "passive"))
    )
    (net (code "68") (name "unconnected-(U1-NC-Pad34)") (class "Default")
      (node (ref "U1") (pin "34") (pinfunction "NC_34") (pintype "passive"))
    )
    (net (code "69") (name "unconnected-(U1-NC-Pad36)") (class "Default")
      (node (ref "U1") (pin "36") (pinfunction "NC_36") (pintype "passive"))
    )
    (net (code "70") (name "unconnected-(U1-NC-Pad39)") (class "Default")
      (node (ref "U1") (pin "39") (pinfunction "NC_39") (pintype "passive"))
    )
    (net (code "71") (name "unconnected-(U1-TEST-Pad2)") (class "Default")
      (node (ref "U1") (pin "2") (pinfunction "TEST_2") (pintype "passive"))
    )
    (net (code "72") (name "unconnected-(U2-NC-Pad11)") (class "Default")
      (node (ref "U2") (pin "11") (pinfunction "NC_11") (pintype "passive"))
    )
    (net (code "73") (name "unconnected-(U2-NC-Pad12)") (class "Default")
      (node (ref "U2") (pin "12") (pinfunction "NC_12") (pintype "passive"))
    )
    (net (code "74") (name "unconnected-(U2-NC-Pad13)") (class "Default")
      (node (ref "U2") (pin "13") (pinfunction "NC_13") (pintype "passive"))
    )
    (net (code "75") (name "unconnected-(U2-NC-Pad14)") (class "Default")
      (node (ref "U2") (pin "14") (pinfunction "NC_14") (pintype "passive"))
    )
    (net (code "76") (name "unconnected-(U2-NC-Pad15)") (class "Default")
      (node (ref "U2") (pin "15") (pinfunction "NC_15") (pintype "passive"))
    )
    (net (code "77") (name "unconnected-(U2-NC-Pad19)") (class "Default")
      (node (ref "U2") (pin "19") (pinfunction "NC_19") (pintype "passive"))
    )
    (net (code "78") (name "unconnected-(U2-NC-Pad21)") (class "Default")
      (node (ref "U2") (pin "21") (pinfunction "NC_21") (pintype "passive"))
    )
    (net (code "79") (name "unconnected-(U2-NC-Pad27)") (class "Default")
      (node (ref "U2") (pin "27") (pinfunction "NC_27") (pintype "passive"))
    )
    (net (code "80") (name "unconnected-(U2-NC-Pad29)") (class "Default")
      (node (ref "U2") (pin "29") (pinfunction "NC_29") (pintype "passive"))
    )
    (net (code "81") (name "unconnected-(U2-NC-Pad32)") (class "Default")
      (node (ref "U2") (pin "32") (pinfunction "NC_32") (pintype "passive"))
    )
    (net (code "82") (name "unconnected-(U2-NC-Pad33)") (class "Default")
      (node (ref "U2") (pin "33") (pinfunction "NC_33") (pintype "passive"))
    )
    (net (code "83") (name "unconnected-(U2-NC-Pad34)") (class "Default")
      (node (ref "U2") (pin "34") (pinfunction "NC_34") (pintype "passive"))
    )
    (net (code "84") (name "unconnected-(U2-NC-Pad36)") (class "Default")
      (node (ref "U2") (pin "36") (pinfunction "NC_36") (pintype "passive"))
    )
    (net (code "85") (name "unconnected-(U2-NC-Pad39)") (class "Default")
      (node (ref "U2") (pin "39") (pinfunction "NC_39") (pintype "passive"))
    )
    (net (code "86") (name "unconnected-(U2-TEST-Pad2)") (class "Default")
      (node (ref "U2") (pin "2") (pinfunction "TEST_2") (pintype "passive"))
    )
  )
)
